# BusPirate-v36.net
KiCad netlist of a schematic drawn in EAGLE
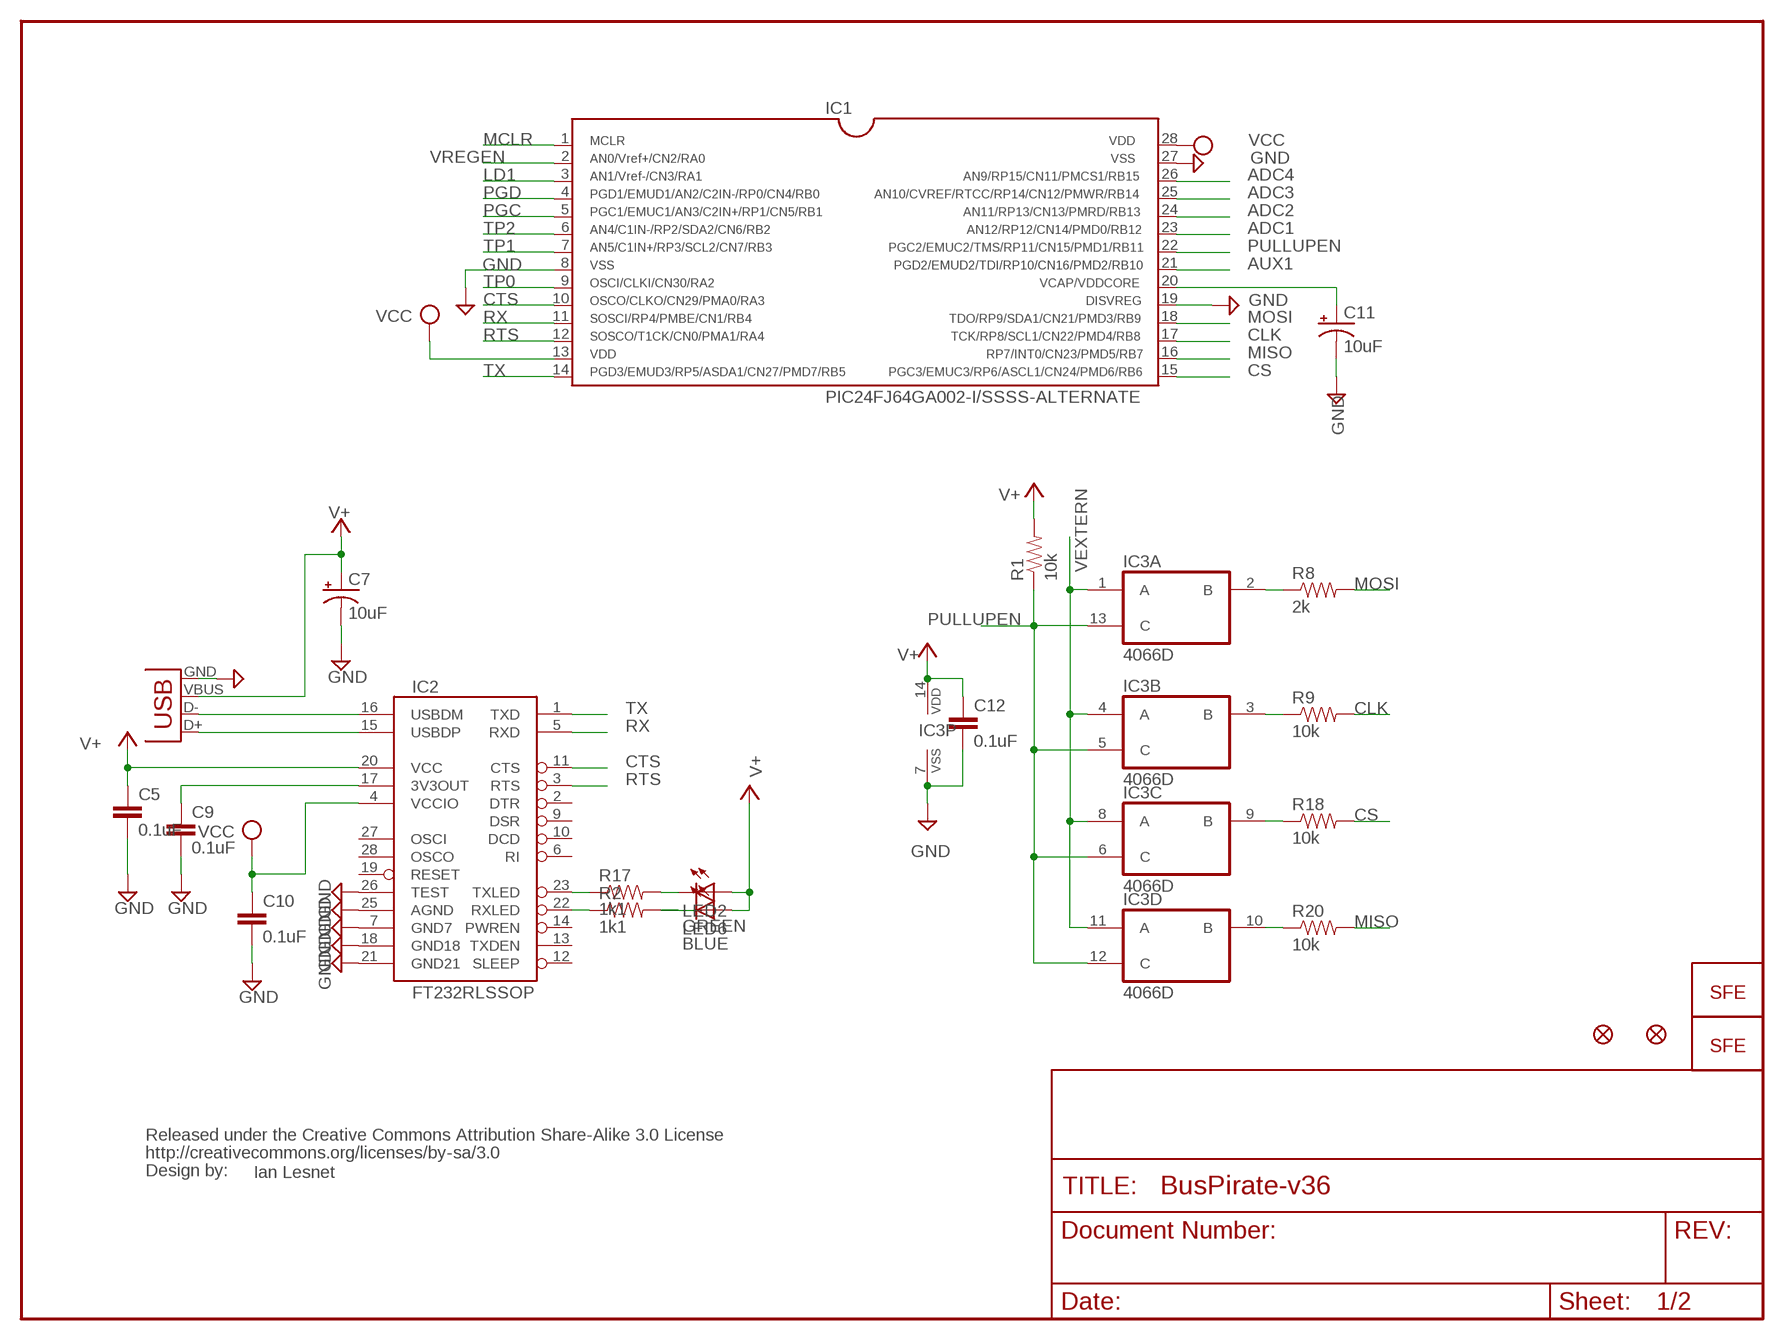
[diagram p0: schematic, sheet 1]
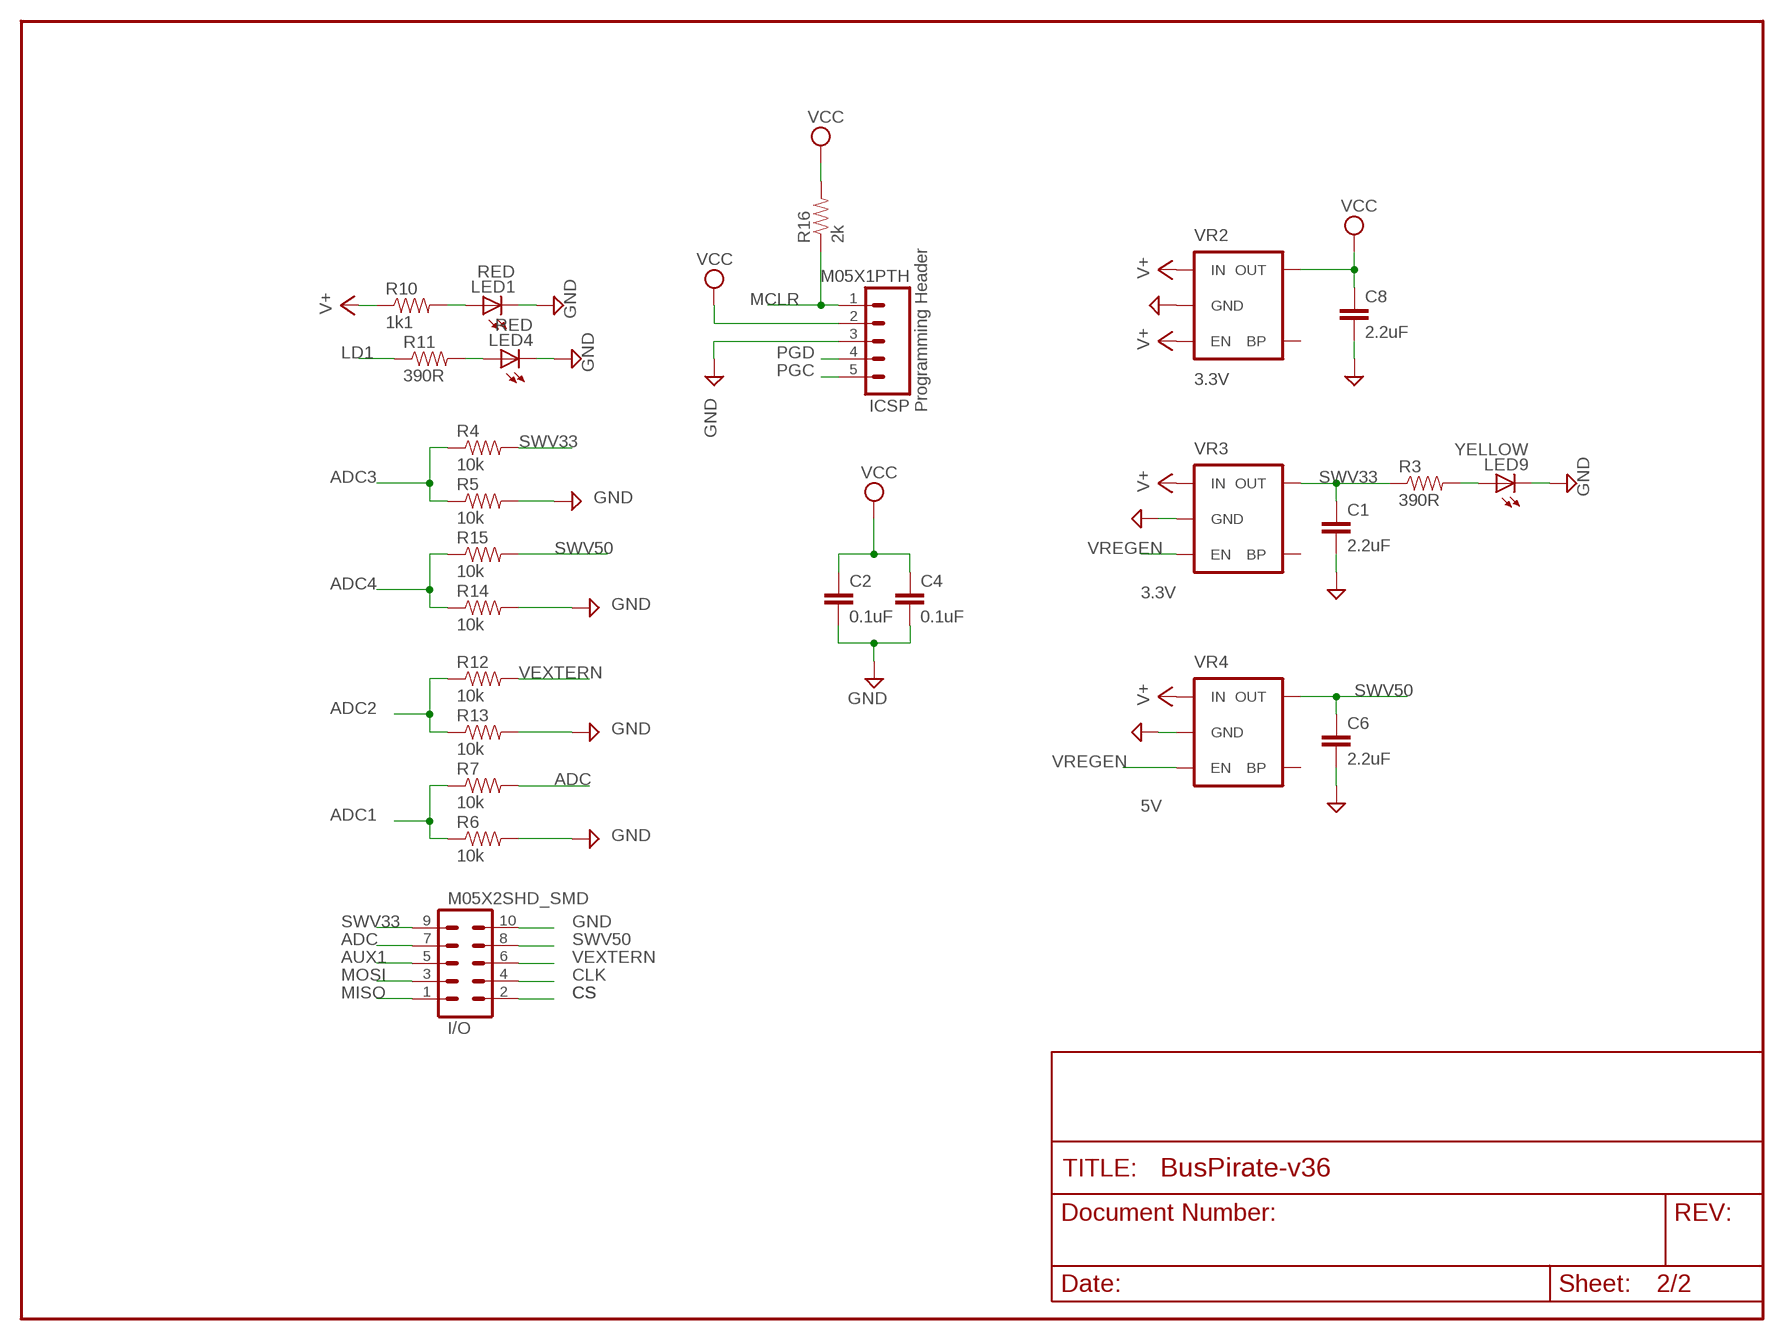
[diagram p1: schematic, sheet 2]

(export (version "E")
  (design (tool "Eeschema 10.0.6"))
  (components
    (comp (ref "C1")
      (value "2.2uF")
      (footprint "eagle-import:0402-CAP")
      (libsource (lib "eagle-import") (part "CAP0402-CAP"))
    )
    (comp (ref "C2")
      (value "0.1uF")
      (footprint "eagle-import:0402-CAP")
      (libsource (lib "eagle-import") (part "CAP0402-CAP"))
    )
    (comp (ref "C4")
      (value "0.1uF")
      (footprint "eagle-import:0402-CAP")
      (libsource (lib "eagle-import") (part "CAP0402-CAP"))
    )
    (comp (ref "C6")
      (value "2.2uF")
      (footprint "eagle-import:0402-CAP")
      (libsource (lib "eagle-import") (part "CAP0402-CAP"))
    )
    (comp (ref "C8")
      (value "2.2uF")
      (footprint "eagle-import:0402-CAP")
      (libsource (lib "eagle-import") (part "CAP0402-CAP"))
    )
    (comp (ref "I/O")
      (value "M05X2SHD_SMD")
      (footprint "eagle-import:2X5-SHROUDED_SMD")
      (libsource (lib "eagle-import") (part "M05X2SHD_SMD"))
    )
    (comp (ref "ICSP")
      (value "M05X1PTH")
      (footprint "eagle-import:1X05")
      (libsource (lib "eagle-import") (part "M05PTH"))
    )
    (comp (ref "LED1")
      (value "RED")
      (footprint "eagle-import:LED-0603")
      (libsource (lib "eagle-import") (part "LED0603"))
    )
    (comp (ref "LED4")
      (value "RED")
      (footprint "eagle-import:LED-0603")
      (libsource (lib "eagle-import") (part "LED0603"))
    )
    (comp (ref "LED9")
      (value "YELLOW")
      (footprint "eagle-import:LED-0603")
      (libsource (lib "eagle-import") (part "LED0603"))
    )
    (comp (ref "R3")
      (value "390R")
      (footprint "eagle-import:0402-RES")
      (libsource (lib "eagle-import") (part "RESISTOR0402-RES"))
    )
    (comp (ref "R4")
      (value "10k")
      (footprint "eagle-import:0402-RES")
      (libsource (lib "eagle-import") (part "RESISTOR0402-RES"))
    )
    (comp (ref "R5")
      (value "10k")
      (footprint "eagle-import:0402-RES")
      (libsource (lib "eagle-import") (part "RESISTOR0402-RES"))
    )
    (comp (ref "R6")
      (value "10k")
      (footprint "eagle-import:0402-RES")
      (libsource (lib "eagle-import") (part "RESISTOR0402-RES"))
    )
    (comp (ref "R7")
      (value "10k")
      (footprint "eagle-import:0402-RES")
      (libsource (lib "eagle-import") (part "RESISTOR0402-RES"))
    )
    (comp (ref "R10")
      (value "1k1")
      (footprint "eagle-import:0402-RES")
      (libsource (lib "eagle-import") (part "RESISTOR0402-RES"))
    )
    (comp (ref "R11")
      (value "390R")
      (footprint "eagle-import:0402-RES")
      (libsource (lib "eagle-import") (part "RESISTOR0402-RES"))
    )
    (comp (ref "R12")
      (value "10k")
      (footprint "eagle-import:0402-RES")
      (libsource (lib "eagle-import") (part "RESISTOR0402-RES"))
    )
    (comp (ref "R13")
      (value "10k")
      (footprint "eagle-import:0402-RES")
      (libsource (lib "eagle-import") (part "RESISTOR0402-RES"))
    )
    (comp (ref "R14")
      (value "10k")
      (footprint "eagle-import:0402-RES")
      (libsource (lib "eagle-import") (part "RESISTOR0402-RES"))
    )
    (comp (ref "R15")
      (value "10k")
      (footprint "eagle-import:0402-RES")
      (libsource (lib "eagle-import") (part "RESISTOR0402-RES"))
    )
    (comp (ref "R16")
      (value "2k")
      (footprint "eagle-import:0402-RES")
      (libsource (lib "eagle-import") (part "RESISTOR0402-RES"))
    )
    (comp (ref "VR2")
      (value "3.3V")
      (footprint "eagle-import:SOT23-5")
      (libsource (lib "eagle-import") (part "V_REG_LDOSMD"))
    )
    (comp (ref "VR3")
      (value "3.3V")
      (footprint "eagle-import:SOT23-5")
      (libsource (lib "eagle-import") (part "V_REG_LDOSMD"))
    )
    (comp (ref "VR4")
      (value "5V")
      (footprint "eagle-import:SOT23-5")
      (libsource (lib "eagle-import") (part "V_REG_LDOSMD"))
    )
    (comp (ref "C5")
      (value "0.1uF")
      (footprint "eagle-import:0402-CAP")
      (libsource (lib "eagle-import") (part "CAP0402-CAP"))
    )
    (comp (ref "C7")
      (value "10uF")
      (footprint "eagle-import:EIA3216")
      (libsource (lib "eagle-import") (part "CAP_POL1206"))
    )
    (comp (ref "C9")
      (value "0.1uF")
      (footprint "eagle-import:0402-CAP")
      (libsource (lib "eagle-import") (part "CAP0402-CAP"))
    )
    (comp (ref "C10")
      (value "0.1uF")
      (footprint "eagle-import:0402-CAP")
      (libsource (lib "eagle-import") (part "CAP0402-CAP"))
    )
    (comp (ref "C11")
      (value "10uF")
      (footprint "eagle-import:EIA3216")
      (libsource (lib "eagle-import") (part "CAP_POL1206"))
    )
    (comp (ref "C12")
      (value "0.1uF")
      (footprint "eagle-import:0402-CAP")
      (libsource (lib "eagle-import") (part "CAP0402-CAP"))
    )
    (comp (ref "IC1")
      (value "PIC24FJ64GA002-I/SSSS-ALTERNATE")
      (footprint "eagle-import:SSOP28DB")
      (libsource (lib "eagle-import") (part "PIC24FJ64GA002-I/SSSS-ALTERNATE"))
    )
    (comp (ref "IC2")
      (value "FT232RLSSOP")
      (footprint "eagle-import:SSOP28DB")
      (libsource (lib "eagle-import") (part "FT232RLSSOP"))
    )
    (comp (ref "IC3")
      (value "4066D")
      (footprint "eagle-import:SO14")
      (libsource (lib "eagle-import") (part "4066D"))
    )
    (comp (ref "J1")
      (value "USBSMD")
      (footprint "eagle-import:USB-MINIB")
      (libsource (lib "eagle-import") (part "USBSMD"))
    )
    (comp (ref "JP1")
      (value "LOGO-SFENEW")
      (footprint "eagle-import:SFE-NEW-WEBLOGO")
      (libsource (lib "eagle-import") (part "LOGO-SFENEW"))
    )
    (comp (ref "JP2")
      (value "LOGO-SFENEW")
      (footprint "eagle-import:SFE-NEW-WEBLOGO")
      (libsource (lib "eagle-import") (part "LOGO-SFENEW"))
    )
    (comp (ref "JP3")
      (value "FIDUCIAL1X2")
      (footprint "eagle-import:FIDUCIAL-1X2")
      (libsource (lib "eagle-import") (part "FIDUCIAL1X2"))
    )
    (comp (ref "JP4")
      (value "FIDUCIAL1X2")
      (footprint "eagle-import:FIDUCIAL-1X2")
      (libsource (lib "eagle-import") (part "FIDUCIAL1X2"))
    )
    (comp (ref "LED2")
      (value "GREEN")
      (footprint "eagle-import:LED-0603")
      (libsource (lib "eagle-import") (part "LED0603"))
    )
    (comp (ref "LED6")
      (value "BLUE")
      (footprint "eagle-import:LED-0603")
      (libsource (lib "eagle-import") (part "LED0603"))
    )
    (comp (ref "R1")
      (value "10k")
      (footprint "eagle-import:0402-RES")
      (libsource (lib "eagle-import") (part "RESISTOR0402-RES"))
    )
    (comp (ref "R2")
      (value "1k1")
      (footprint "eagle-import:0402-RES")
      (libsource (lib "eagle-import") (part "RESISTOR0402-RES"))
    )
    (comp (ref "R8")
      (value "2k")
      (footprint "eagle-import:0402-RES")
      (libsource (lib "eagle-import") (part "RESISTOR0402-RES"))
    )
    (comp (ref "R9")
      (value "10k")
      (footprint "eagle-import:0402-RES")
      (libsource (lib "eagle-import") (part "RESISTOR0402-RES"))
    )
    (comp (ref "R17")
      (value "1k1")
      (footprint "eagle-import:0402-RES")
      (libsource (lib "eagle-import") (part "RESISTOR0402-RES"))
    )
    (comp (ref "R18")
      (value "10k")
      (footprint "eagle-import:0402-RES")
      (libsource (lib "eagle-import") (part "RESISTOR0402-RES"))
    )
    (comp (ref "R20")
      (value "10k")
      (footprint "eagle-import:0402-RES")
      (libsource (lib "eagle-import") (part "RESISTOR0402-RES"))
    )
    (comp (ref "U$2")
      (value "CREATIVE_COMMONS")
      (footprint "eagle-import:CREATIVE_COMMONS")
      (libsource (lib "eagle-import") (part "CREATIVE_COMMONS"))
    )
  )
  (nets
    (net (code "1") (name "ADC") (class "Default")
      (node (ref "I/O") (pin "7") (pinfunction "7_7") (pintype "passive"))
      (node (ref "R7") (pin "2") (pinfunction "2_2") (pintype "passive"))
    )
    (net (code "2") (name "ADC1") (class "Default")
      (node (ref "IC1") (pin "23") (pinfunction "23_23") (pintype "passive"))
      (node (ref "R6") (pin "1") (pinfunction "1_1") (pintype "passive"))
      (node (ref "R7") (pin "1") (pinfunction "1_1") (pintype "passive"))
    )
    (net (code "3") (name "ADC2") (class "Default")
      (node (ref "IC1") (pin "24") (pinfunction "24_24") (pintype "passive"))
      (node (ref "R12") (pin "1") (pinfunction "1_1") (pintype "passive"))
      (node (ref "R13") (pin "1") (pinfunction "1_1") (pintype "passive"))
    )
    (net (code "4") (name "ADC3") (class "Default")
      (node (ref "IC1") (pin "25") (pinfunction "25_25") (pintype "passive"))
      (node (ref "R4") (pin "1") (pinfunction "1_1") (pintype "passive"))
      (node (ref "R5") (pin "1") (pinfunction "1_1") (pintype "passive"))
    )
    (net (code "5") (name "ADC4") (class "Default")
      (node (ref "IC1") (pin "26") (pinfunction "26_26") (pintype "passive"))
      (node (ref "R14") (pin "1") (pinfunction "1_1") (pintype "passive"))
      (node (ref "R15") (pin "1") (pinfunction "1_1") (pintype "passive"))
    )
    (net (code "6") (name "AUX1") (class "Default")
      (node (ref "I/O") (pin "5") (pinfunction "5_5") (pintype "passive"))
      (node (ref "IC1") (pin "21") (pinfunction "21_21") (pintype "passive"))
    )
    (net (code "7") (name "CLK") (class "Default")
      (node (ref "I/O") (pin "4") (pinfunction "4_4") (pintype "passive"))
      (node (ref "IC1") (pin "17") (pinfunction "17_17") (pintype "passive"))
      (node (ref "R9") (pin "2") (pinfunction "2_2") (pintype "passive"))
    )
    (net (code "8") (name "CS") (class "Default")
      (node (ref "I/O") (pin "2") (pinfunction "2_2") (pintype "passive"))
      (node (ref "IC1") (pin "15") (pinfunction "15_15") (pintype "passive"))
      (node (ref "R18") (pin "2") (pinfunction "2_2") (pintype "passive"))
    )
    (net (code "9") (name "CTS") (class "Default")
      (node (ref "IC1") (pin "10") (pinfunction "10_10") (pintype "passive"))
      (node (ref "IC2") (pin "11") (pinfunction "CTS_11") (pintype "input"))
    )
    (net (code "10") (name "GND") (class "Default")
      (node (ref "C1") (pin "2") (pinfunction "2_2") (pintype "passive"))
      (node (ref "C10") (pin "2") (pinfunction "2_2") (pintype "passive"))
      (node (ref "C11") (pin "C") (pinfunction "-_C") (pintype "passive"))
      (node (ref "C12") (pin "2") (pinfunction "2_2") (pintype "passive"))
      (node (ref "C2") (pin "2") (pinfunction "2_2") (pintype "passive"))
      (node (ref "C4") (pin "2") (pinfunction "2_2") (pintype "passive"))
      (node (ref "C5") (pin "2") (pinfunction "2_2") (pintype "passive"))
      (node (ref "C6") (pin "2") (pinfunction "2_2") (pintype "passive"))
      (node (ref "C7") (pin "C") (pinfunction "-_C") (pintype "passive"))
      (node (ref "C8") (pin "2") (pinfunction "2_2") (pintype "passive"))
      (node (ref "C9") (pin "2") (pinfunction "2_2") (pintype "passive"))
      (node (ref "I/O") (pin "10") (pinfunction "10_10") (pintype "passive"))
      (node (ref "IC1") (pin "19") (pinfunction "19_19") (pintype "passive"))
      (node (ref "IC1") (pin "27") (pinfunction "27_27") (pintype "passive"))
      (node (ref "IC1") (pin "8") (pinfunction "8_8") (pintype "passive"))
      (node (ref "IC2") (pin "18") (pinfunction "GND18_18") (pintype "power_in"))
      (node (ref "IC2") (pin "21") (pinfunction "GND21_21") (pintype "power_in"))
      (node (ref "IC2") (pin "25") (pinfunction "AGND_25") (pintype "power_in"))
      (node (ref "IC2") (pin "26") (pinfunction "TEST_26") (pintype "input"))
      (node (ref "IC2") (pin "7") (pinfunction "GND7_7") (pintype "power_in"))
      (node (ref "IC3") (pin "7") (pinfunction "VSS_7") (pintype "power_in"))
      (node (ref "ICSP") (pin "3") (pinfunction "3_3") (pintype "passive"))
      (node (ref "J1") (pin "GND") (pinfunction "GND_GND") (pintype "bidirectional"))
      (node (ref "LED1") (pin "C") (pinfunction "C_C") (pintype "passive"))
      (node (ref "LED4") (pin "C") (pinfunction "C_C") (pintype "passive"))
      (node (ref "LED9") (pin "C") (pinfunction "C_C") (pintype "passive"))
      (node (ref "R13") (pin "2") (pinfunction "2_2") (pintype "passive"))
      (node (ref "R14") (pin "2") (pinfunction "2_2") (pintype "passive"))
      (node (ref "R5") (pin "2") (pinfunction "2_2") (pintype "passive"))
      (node (ref "R6") (pin "2") (pinfunction "2_2") (pintype "passive"))
      (node (ref "VR2") (pin "2") (pinfunction "GND_2") (pintype "input"))
      (node (ref "VR3") (pin "2") (pinfunction "GND_2") (pintype "input"))
      (node (ref "VR4") (pin "2") (pinfunction "GND_2") (pintype "input"))
    )
    (net (code "11") (name "LD1") (class "Default")
      (node (ref "IC1") (pin "3") (pinfunction "3_3") (pintype "passive"))
      (node (ref "R11") (pin "1") (pinfunction "1_1") (pintype "passive"))
    )
    (net (code "12") (name "MCLR") (class "Default")
      (node (ref "IC1") (pin "1") (pinfunction "1_1") (pintype "passive"))
      (node (ref "ICSP") (pin "1") (pinfunction "1_1") (pintype "passive"))
      (node (ref "R16") (pin "1") (pinfunction "1_1") (pintype "passive"))
    )
    (net (code "13") (name "MISO") (class "Default")
      (node (ref "I/O") (pin "1") (pinfunction "1_1") (pintype "passive"))
      (node (ref "IC1") (pin "16") (pinfunction "16_16") (pintype "passive"))
      (node (ref "R20") (pin "2") (pinfunction "2_2") (pintype "passive"))
    )
    (net (code "14") (name "MOSI") (class "Default")
      (node (ref "I/O") (pin "3") (pinfunction "3_3") (pintype "passive"))
      (node (ref "IC1") (pin "18") (pinfunction "18_18") (pintype "passive"))
      (node (ref "R8") (pin "2") (pinfunction "2_2") (pintype "passive"))
    )
    (net (code "15") (name "Net-(C11-+)") (class "Default")
      (node (ref "C11") (pin "A") (pinfunction "+_A") (pintype "passive"))
      (node (ref "IC1") (pin "20") (pinfunction "20_20") (pintype "passive"))
    )
    (net (code "16") (name "Net-(IC2-3V3OUT)") (class "Default")
      (node (ref "C9") (pin "1") (pinfunction "1_1") (pintype "passive"))
      (node (ref "IC2") (pin "17") (pinfunction "3V3OUT_17") (pintype "output"))
    )
    (net (code "17") (name "Net-(IC2-RXLED)") (class "Default")
      (node (ref "IC2") (pin "22") (pinfunction "RXLED_22") (pintype "input"))
      (node (ref "R2") (pin "1") (pinfunction "1_1") (pintype "passive"))
    )
    (net (code "18") (name "Net-(IC2-TXLED)") (class "Default")
      (node (ref "IC2") (pin "23") (pinfunction "TXLED_23") (pintype "input"))
      (node (ref "R17") (pin "1") (pinfunction "1_1") (pintype "passive"))
    )
    (net (code "19") (name "Net-(IC2-USBDM)") (class "Default")
      (node (ref "IC2") (pin "16") (pinfunction "USBDM_16") (pintype "bidirectional"))
      (node (ref "J1") (pin "D-") (pinfunction "D-_D-") (pintype "bidirectional"))
    )
    (net (code "20") (name "Net-(IC2-USBDP)") (class "Default")
      (node (ref "IC2") (pin "15") (pinfunction "USBDP_15") (pintype "bidirectional"))
      (node (ref "J1") (pin "D+") (pinfunction "D+_D+") (pintype "bidirectional"))
    )
    (net (code "21") (name "Net-(IC3A-B)") (class "Default")
      (node (ref "IC3") (pin "2") (pinfunction "B_2") (pintype "tri_state"))
      (node (ref "R8") (pin "1") (pinfunction "1_1") (pintype "passive"))
    )
    (net (code "22") (name "Net-(IC3B-B)") (class "Default")
      (node (ref "IC3") (pin "3") (pinfunction "B_3") (pintype "tri_state"))
      (node (ref "R9") (pin "1") (pinfunction "1_1") (pintype "passive"))
    )
    (net (code "23") (name "Net-(IC3C-B)") (class "Default")
      (node (ref "IC3") (pin "9") (pinfunction "B_9") (pintype "tri_state"))
      (node (ref "R18") (pin "1") (pinfunction "1_1") (pintype "passive"))
    )
    (net (code "24") (name "Net-(IC3D-B)") (class "Default")
      (node (ref "IC3") (pin "10") (pinfunction "B_10") (pintype "tri_state"))
      (node (ref "R20") (pin "1") (pinfunction "1_1") (pintype "passive"))
    )
    (net (code "25") (name "Net-(LED1-PadA)") (class "Default")
      (node (ref "LED1") (pin "A") (pinfunction "A_A") (pintype "passive"))
      (node (ref "R10") (pin "2") (pinfunction "2_2") (pintype "passive"))
    )
    (net (code "26") (name "Net-(LED2-PadC)") (class "Default")
      (node (ref "LED2") (pin "C") (pinfunction "C_C") (pintype "passive"))
      (node (ref "R17") (pin "2") (pinfunction "2_2") (pintype "passive"))
    )
    (net (code "27") (name "Net-(LED4-PadA)") (class "Default")
      (node (ref "LED4") (pin "A") (pinfunction "A_A") (pintype "passive"))
      (node (ref "R11") (pin "2") (pinfunction "2_2") (pintype "passive"))
    )
    (net (code "28") (name "Net-(LED6-PadC)") (class "Default")
      (node (ref "LED6") (pin "C") (pinfunction "C_C") (pintype "passive"))
      (node (ref "R2") (pin "2") (pinfunction "2_2") (pintype "passive"))
    )
    (net (code "29") (name "Net-(LED9-PadA)") (class "Default")
      (node (ref "LED9") (pin "A") (pinfunction "A_A") (pintype "passive"))
      (node (ref "R3") (pin "2") (pinfunction "2_2") (pintype "passive"))
    )
    (net (code "30") (name "PGC") (class "Default")
      (node (ref "IC1") (pin "5") (pinfunction "5_5") (pintype "passive"))
      (node (ref "ICSP") (pin "5") (pinfunction "5_5") (pintype "passive"))
    )
    (net (code "31") (name "PGD") (class "Default")
      (node (ref "IC1") (pin "4") (pinfunction "4_4") (pintype "passive"))
      (node (ref "ICSP") (pin "4") (pinfunction "4_4") (pintype "passive"))
    )
    (net (code "32") (name "PULLUPEN") (class "Default")
      (node (ref "IC1") (pin "22") (pinfunction "22_22") (pintype "passive"))
      (node (ref "IC3") (pin "12") (pinfunction "C_12") (pintype "input"))
      (node (ref "IC3") (pin "13") (pinfunction "C_13") (pintype "input"))
      (node (ref "IC3") (pin "5") (pinfunction "C_5") (pintype "input"))
      (node (ref "IC3") (pin "6") (pinfunction "C_6") (pintype "input"))
      (node (ref "R1") (pin "1") (pinfunction "1_1") (pintype "passive"))
    )
    (net (code "33") (name "RTS") (class "Default")
      (node (ref "IC1") (pin "12") (pinfunction "12_12") (pintype "passive"))
      (node (ref "IC2") (pin "3") (pinfunction "RTS_3") (pintype "output"))
    )
    (net (code "34") (name "RX") (class "Default")
      (node (ref "IC1") (pin "11") (pinfunction "11_11") (pintype "passive"))
      (node (ref "IC2") (pin "5") (pinfunction "RXD_5") (pintype "input"))
    )
    (net (code "35") (name "SWV33") (class "Default")
      (node (ref "C1") (pin "1") (pinfunction "1_1") (pintype "passive"))
      (node (ref "I/O") (pin "9") (pinfunction "9_9") (pintype "passive"))
      (node (ref "R3") (pin "1") (pinfunction "1_1") (pintype "passive"))
      (node (ref "R4") (pin "2") (pinfunction "2_2") (pintype "passive"))
      (node (ref "VR3") (pin "5") (pinfunction "OUT_5") (pintype "passive"))
    )
    (net (code "36") (name "SWV50") (class "Default")
      (node (ref "C6") (pin "1") (pinfunction "1_1") (pintype "passive"))
      (node (ref "I/O") (pin "8") (pinfunction "8_8") (pintype "passive"))
      (node (ref "R15") (pin "2") (pinfunction "2_2") (pintype "passive"))
      (node (ref "VR4") (pin "5") (pinfunction "OUT_5") (pintype "passive"))
    )
    (net (code "37") (name "TP0") (class "Default")
      (node (ref "IC1") (pin "9") (pinfunction "9_9") (pintype "passive"))
    )
    (net (code "38") (name "TP1") (class "Default")
      (node (ref "IC1") (pin "7") (pinfunction "7_7") (pintype "passive"))
    )
    (net (code "39") (name "TP2") (class "Default")
      (node (ref "IC1") (pin "6") (pinfunction "6_6") (pintype "passive"))
    )
    (net (code "40") (name "TX") (class "Default")
      (node (ref "IC1") (pin "14") (pinfunction "14_14") (pintype "passive"))
      (node (ref "IC2") (pin "1") (pinfunction "TXD_1") (pintype "output"))
    )
    (net (code "41") (name "V+") (class "Default")
      (node (ref "C12") (pin "1") (pinfunction "1_1") (pintype "passive"))
      (node (ref "C5") (pin "1") (pinfunction "1_1") (pintype "passive"))
      (node (ref "C7") (pin "A") (pinfunction "+_A") (pintype "passive"))
      (node (ref "IC2") (pin "20") (pinfunction "VCC_20") (pintype "power_in"))
      (node (ref "IC3") (pin "14") (pinfunction "VDD_14") (pintype "power_in"))
      (node (ref "J1") (pin "VBUS") (pinfunction "VBUS_VBUS") (pintype "bidirectional"))
      (node (ref "LED2") (pin "A") (pinfunction "A_A") (pintype "passive"))
      (node (ref "LED6") (pin "A") (pinfunction "A_A") (pintype "passive"))
      (node (ref "R1") (pin "2") (pinfunction "2_2") (pintype "passive"))
      (node (ref "R10") (pin "1") (pinfunction "1_1") (pintype "passive"))
      (node (ref "VR2") (pin "1") (pinfunction "IN_1") (pintype "input"))
      (node (ref "VR2") (pin "3") (pinfunction "EN_3") (pintype "input"))
      (node (ref "VR3") (pin "1") (pinfunction "IN_1") (pintype "input"))
      (node (ref "VR4") (pin "1") (pinfunction "IN_1") (pintype "input"))
    )
    (net (code "42") (name "VCC") (class "Default")
      (node (ref "C10") (pin "1") (pinfunction "1_1") (pintype "passive"))
      (node (ref "C2") (pin "1") (pinfunction "1_1") (pintype "passive"))
      (node (ref "C4") (pin "1") (pinfunction "1_1") (pintype "passive"))
      (node (ref "C8") (pin "1") (pinfunction "1_1") (pintype "passive"))
      (node (ref "IC1") (pin "13") (pinfunction "13_13") (pintype "passive"))
      (node (ref "IC1") (pin "28") (pinfunction "28_28") (pintype "passive"))
      (node (ref "IC2") (pin "4") (pinfunction "VCCIO_4") (pintype "power_in"))
      (node (ref "ICSP") (pin "2") (pinfunction "2_2") (pintype "passive"))
      (node (ref "R16") (pin "2") (pinfunction "2_2") (pintype "passive"))
      (node (ref "VR2") (pin "5") (pinfunction "OUT_5") (pintype "passive"))
    )
    (net (code "43") (name "VEXTERN") (class "Default")
      (node (ref "I/O") (pin "6") (pinfunction "6_6") (pintype "passive"))
      (node (ref "IC3") (pin "1") (pinfunction "A_1") (pintype "tri_state"))
      (node (ref "IC3") (pin "11") (pinfunction "A_11") (pintype "tri_state"))
      (node (ref "IC3") (pin "4") (pinfunction "A_4") (pintype "tri_state"))
      (node (ref "IC3") (pin "8") (pinfunction "A_8") (pintype "tri_state"))
      (node (ref "R12") (pin "2") (pinfunction "2_2") (pintype "passive"))
    )
    (net (code "44") (name "VREGEN") (class "Default")
      (node (ref "IC1") (pin "2") (pinfunction "2_2") (pintype "passive"))
      (node (ref "VR3") (pin "3") (pinfunction "EN_3") (pintype "input"))
      (node (ref "VR4") (pin "3") (pinfunction "EN_3") (pintype "input"))
    )
    (net (code "45") (name "unconnected-(IC2-DCD-Pad10)") (class "Default")
      (node (ref "IC2") (pin "10") (pinfunction "DCD_10") (pintype "input"))
    )
    (net (code "46") (name "unconnected-(IC2-DSR-Pad9)") (class "Default")
      (node (ref "IC2") (pin "9") (pinfunction "DSR_9") (pintype "input"))
    )
    (net (code "47") (name "unconnected-(IC2-DTR-Pad2)") (class "Default")
      (node (ref "IC2") (pin "2") (pinfunction "DTR_2") (pintype "output"))
    )
    (net (code "48") (name "unconnected-(IC2-OSCI-Pad27)") (class "Default")
      (node (ref "IC2") (pin "27") (pinfunction "OSCI_27") (pintype "input"))
    )
    (net (code "49") (name "unconnected-(IC2-OSCO-Pad28)") (class "Default")
      (node (ref "IC2") (pin "28") (pinfunction "OSCO_28") (pintype "output"))
    )
    (net (code "50") (name "unconnected-(IC2-PWREN-Pad14)") (class "Default")
      (node (ref "IC2") (pin "14") (pinfunction "PWREN_14") (pintype "input"))
    )
    (net (code "51") (name "unconnected-(IC2-RESET-Pad19)") (class "Default")
      (node (ref "IC2") (pin "19") (pinfunction "RESET_19") (pintype "input"))
    )
    (net (code "52") (name "unconnected-(IC2-RI-Pad6)") (class "Default")
      (node (ref "IC2") (pin "6") (pinfunction "RI_6") (pintype "input"))
    )
    (net (code "53") (name "unconnected-(IC2-SLEEP-Pad12)") (class "Default")
      (node (ref "IC2") (pin "12") (pinfunction "SLEEP_12") (pintype "input"))
    )
    (net (code "54") (name "unconnected-(IC2-TXDEN-Pad13)") (class "Default")
      (node (ref "IC2") (pin "13") (pinfunction "TXDEN_13") (pintype "input"))
    )
    (net (code "55") (name "unconnected-(VR2-BP-Pad4)") (class "Default")
      (node (ref "VR2") (pin "4") (pinfunction "BP_4") (pintype "input"))
    )
    (net (code "56") (name "unconnected-(VR3-BP-Pad4)") (class "Default")
      (node (ref "VR3") (pin "4") (pinfunction "BP_4") (pintype "input"))
    )
    (net (code "57") (name "unconnected-(VR4-BP-Pad4)") (class "Default")
      (node (ref "VR4") (pin "4") (pinfunction "BP_4") (pintype "input"))
    )
  )
)
